# Analog_Testbed.net
KiCad netlist of a schematic drawn in Altium Designer
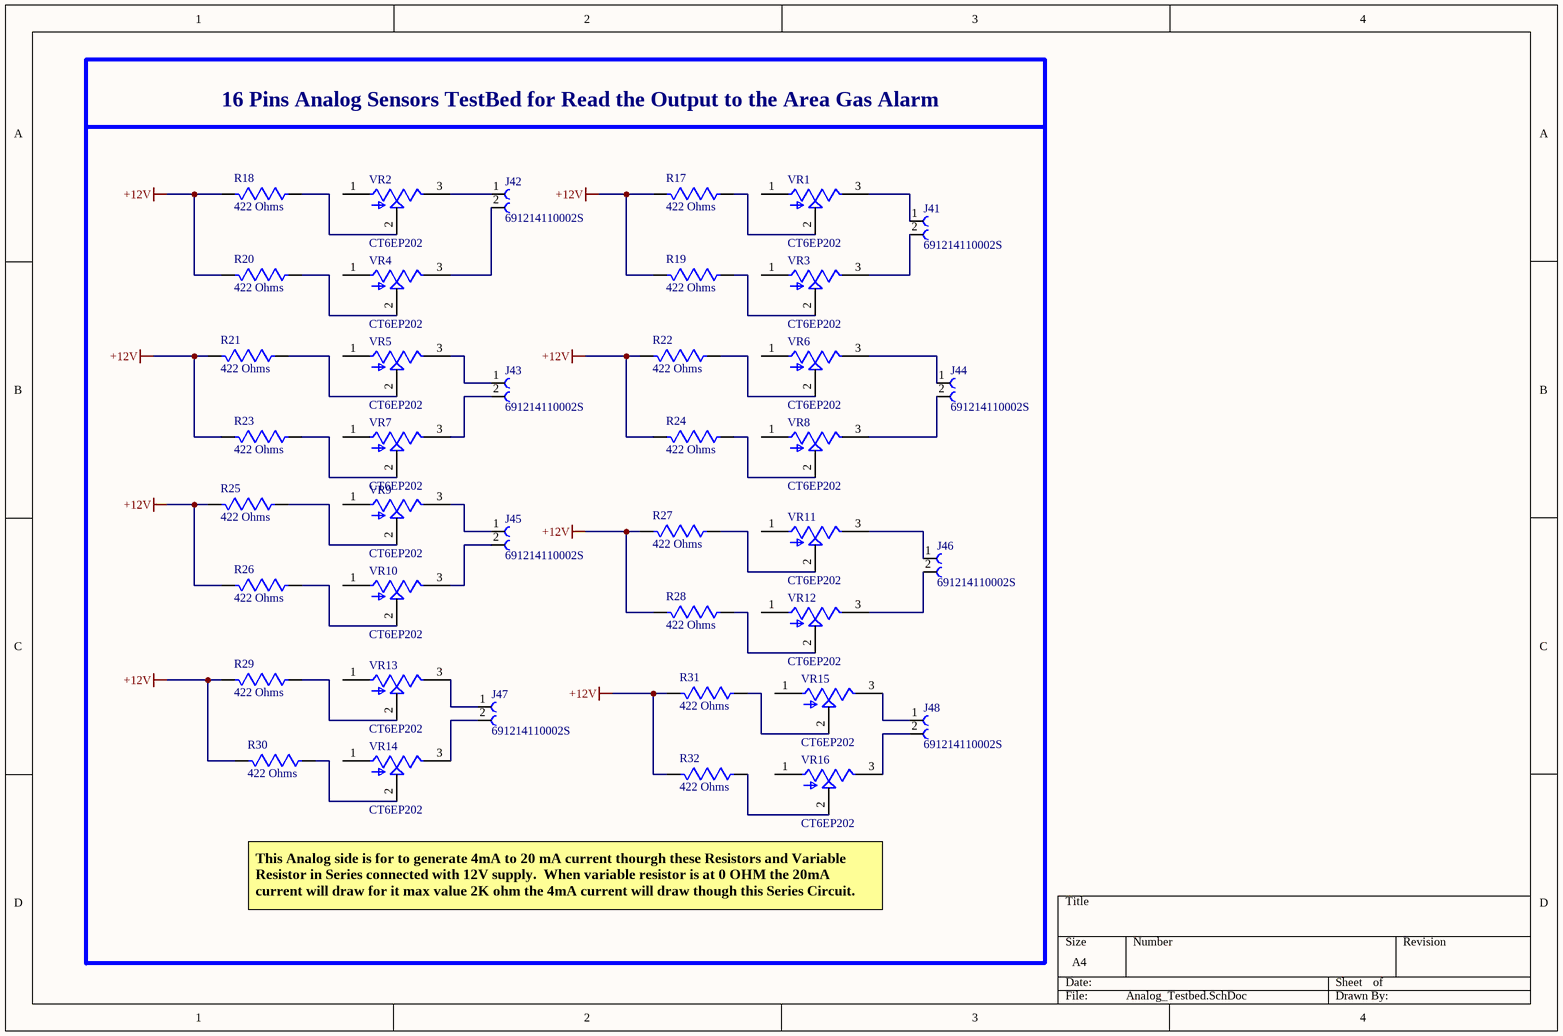
[diagram p0: Analog_Testbed.SchDoc]

(export (version "E")
  (design (tool "Eeschema 10.0.6"))
  (components
    (comp (ref "J41")
      (value "691214110002S")
      (footprint "691214110002S")
      (description "2 Position Wire to Board Terminal Block Horizontal with Board 0.138 (3.50mm) Through Hole")
      (fields (field (name "MF") "WÃ¼rth Elektronik"))
      (libsource (lib "Schlib1") (part "691214110002S"))
    )
    (comp (ref "J42")
      (value "691214110002S")
      (footprint "691214110002S")
      (description "2 Position Wire to Board Terminal Block Horizontal with Board 0.138 (3.50mm) Through Hole")
      (fields (field (name "MF") "WÃ¼rth Elektronik"))
      (libsource (lib "Schlib1") (part "691214110002S"))
    )
    (comp (ref "J43")
      (value "691214110002S")
      (footprint "691214110002S")
      (description "2 Position Wire to Board Terminal Block Horizontal with Board 0.138 (3.50mm) Through Hole")
      (fields (field (name "MF") "WÃ¼rth Elektronik"))
      (libsource (lib "Schlib1") (part "691214110002S"))
    )
    (comp (ref "J44")
      (value "691214110002S")
      (footprint "691214110002S")
      (description "2 Position Wire to Board Terminal Block Horizontal with Board 0.138 (3.50mm) Through Hole")
      (fields (field (name "MF") "WÃ¼rth Elektronik"))
      (libsource (lib "Schlib1") (part "691214110002S"))
    )
    (comp (ref "J45")
      (value "691214110002S")
      (footprint "691214110002S")
      (description "2 Position Wire to Board Terminal Block Horizontal with Board 0.138 (3.50mm) Through Hole")
      (fields (field (name "MF") "WÃ¼rth Elektronik"))
      (libsource (lib "Schlib1") (part "691214110002S"))
    )
    (comp (ref "J46")
      (value "691214110002S")
      (footprint "691214110002S")
      (description "2 Position Wire to Board Terminal Block Horizontal with Board 0.138 (3.50mm) Through Hole")
      (fields (field (name "MF") "WÃ¼rth Elektronik"))
      (libsource (lib "Schlib1") (part "691214110002S"))
    )
    (comp (ref "J47")
      (value "691214110002S")
      (footprint "691214110002S")
      (description "2 Position Wire to Board Terminal Block Horizontal with Board 0.138 (3.50mm) Through Hole")
      (fields (field (name "MF") "WÃ¼rth Elektronik"))
      (libsource (lib "Schlib1") (part "691214110002S"))
    )
    (comp (ref "J48")
      (value "691214110002S")
      (footprint "691214110002S")
      (description "2 Position Wire to Board Terminal Block Horizontal with Board 0.138 (3.50mm) Through Hole")
      (fields (field (name "MF") "WÃ¼rth Elektronik"))
      (libsource (lib "Schlib1") (part "691214110002S"))
    )
    (comp (ref "R17")
      (value "422 Ohms")
      (footprint "RES_422")
      (description "1W Thick Film Resistors 200V ±100ppm/℃ ±1% -55℃~+155℃ 422Ω 2512 Chip Resistor - Surface Mount ROHS")
      (libsource (lib "Schlib1") (part "RES_422"))
    )
    (comp (ref "R18")
      (value "422 Ohms")
      (footprint "RES_422")
      (description "1W Thick Film Resistors 200V ±100ppm/℃ ±1% -55℃~+155℃ 422Ω 2512 Chip Resistor - Surface Mount ROHS")
      (libsource (lib "Schlib1") (part "RES_422"))
    )
    (comp (ref "R19")
      (value "422 Ohms")
      (footprint "RES_422")
      (description "1W Thick Film Resistors 200V ±100ppm/℃ ±1% -55℃~+155℃ 422Ω 2512 Chip Resistor - Surface Mount ROHS")
      (libsource (lib "Schlib1") (part "RES_422"))
    )
    (comp (ref "R20")
      (value "422 Ohms")
      (footprint "RES_422")
      (description "1W Thick Film Resistors 200V ±100ppm/℃ ±1% -55℃~+155℃ 422Ω 2512 Chip Resistor - Surface Mount ROHS")
      (libsource (lib "Schlib1") (part "RES_422"))
    )
    (comp (ref "R21")
      (value "422 Ohms")
      (footprint "RES_422")
      (description "1W Thick Film Resistors 200V ±100ppm/℃ ±1% -55℃~+155℃ 422Ω 2512 Chip Resistor - Surface Mount ROHS")
      (libsource (lib "Schlib1") (part "RES_422"))
    )
    (comp (ref "R22")
      (value "422 Ohms")
      (footprint "RES_422")
      (description "1W Thick Film Resistors 200V ±100ppm/℃ ±1% -55℃~+155℃ 422Ω 2512 Chip Resistor - Surface Mount ROHS")
      (libsource (lib "Schlib1") (part "RES_422"))
    )
    (comp (ref "R23")
      (value "422 Ohms")
      (footprint "RES_422")
      (description "1W Thick Film Resistors 200V ±100ppm/℃ ±1% -55℃~+155℃ 422Ω 2512 Chip Resistor - Surface Mount ROHS")
      (libsource (lib "Schlib1") (part "RES_422"))
    )
    (comp (ref "R24")
      (value "422 Ohms")
      (footprint "RES_422")
      (description "1W Thick Film Resistors 200V ±100ppm/℃ ±1% -55℃~+155℃ 422Ω 2512 Chip Resistor - Surface Mount ROHS")
      (libsource (lib "Schlib1") (part "RES_422"))
    )
    (comp (ref "R25")
      (value "422 Ohms")
      (footprint "RES_422")
      (description "1W Thick Film Resistors 200V ±100ppm/℃ ±1% -55℃~+155℃ 422Ω 2512 Chip Resistor - Surface Mount ROHS")
      (libsource (lib "Schlib1") (part "RES_422"))
    )
    (comp (ref "R26")
      (value "422 Ohms")
      (footprint "RES_422")
      (description "1W Thick Film Resistors 200V ±100ppm/℃ ±1% -55℃~+155℃ 422Ω 2512 Chip Resistor - Surface Mount ROHS")
      (libsource (lib "Schlib1") (part "RES_422"))
    )
    (comp (ref "R27")
      (value "422 Ohms")
      (footprint "RES_422")
      (description "1W Thick Film Resistors 200V ±100ppm/℃ ±1% -55℃~+155℃ 422Ω 2512 Chip Resistor - Surface Mount ROHS")
      (libsource (lib "Schlib1") (part "RES_422"))
    )
    (comp (ref "R28")
      (value "422 Ohms")
      (footprint "RES_422")
      (description "1W Thick Film Resistors 200V ±100ppm/℃ ±1% -55℃~+155℃ 422Ω 2512 Chip Resistor - Surface Mount ROHS")
      (libsource (lib "Schlib1") (part "RES_422"))
    )
    (comp (ref "R29")
      (value "422 Ohms")
      (footprint "RES_422")
      (description "1W Thick Film Resistors 200V ±100ppm/℃ ±1% -55℃~+155℃ 422Ω 2512 Chip Resistor - Surface Mount ROHS")
      (libsource (lib "Schlib1") (part "RES_422"))
    )
    (comp (ref "R30")
      (value "422 Ohms")
      (footprint "RES_422")
      (description "1W Thick Film Resistors 200V ±100ppm/℃ ±1% -55℃~+155℃ 422Ω 2512 Chip Resistor - Surface Mount ROHS")
      (libsource (lib "Schlib1") (part "RES_422"))
    )
    (comp (ref "R31")
      (value "422 Ohms")
      (footprint "RES_422")
      (description "1W Thick Film Resistors 200V ±100ppm/℃ ±1% -55℃~+155℃ 422Ω 2512 Chip Resistor - Surface Mount ROHS")
      (libsource (lib "Schlib1") (part "RES_422"))
    )
    (comp (ref "R32")
      (value "422 Ohms")
      (footprint "RES_422")
      (description "1W Thick Film Resistors 200V ±100ppm/℃ ±1% -55℃~+155℃ 422Ω 2512 Chip Resistor - Surface Mount ROHS")
      (libsource (lib "Schlib1") (part "RES_422"))
    )
    (comp (ref "VR1") (value "CT6EP202") (footprint "CT6EP202") (libsource (lib "Schlib1") (part "CT6EP202")))
    (comp (ref "VR2") (value "CT6EP202") (footprint "CT6EP202") (libsource (lib "Schlib1") (part "CT6EP202")))
    (comp (ref "VR3") (value "CT6EP202") (footprint "CT6EP202") (libsource (lib "Schlib1") (part "CT6EP202")))
    (comp (ref "VR4") (value "CT6EP202") (footprint "CT6EP202") (libsource (lib "Schlib1") (part "CT6EP202")))
    (comp (ref "VR5") (value "CT6EP202") (footprint "CT6EP202") (libsource (lib "Schlib1") (part "CT6EP202")))
    (comp (ref "VR6") (value "CT6EP202") (footprint "CT6EP202") (libsource (lib "Schlib1") (part "CT6EP202")))
    (comp (ref "VR7") (value "CT6EP202") (footprint "CT6EP202") (libsource (lib "Schlib1") (part "CT6EP202")))
    (comp (ref "VR8") (value "CT6EP202") (footprint "CT6EP202") (libsource (lib "Schlib1") (part "CT6EP202")))
    (comp (ref "VR9") (value "CT6EP202") (footprint "CT6EP202") (libsource (lib "Schlib1") (part "CT6EP202")))
    (comp (ref "VR10")
      (value "CT6EP202")
      (footprint "CT6EP202")
      (libsource (lib "Schlib1") (part "CT6EP202"))
    )
    (comp (ref "VR11")
      (value "CT6EP202")
      (footprint "CT6EP202")
      (libsource (lib "Schlib1") (part "CT6EP202"))
    )
    (comp (ref "VR12")
      (value "CT6EP202")
      (footprint "CT6EP202")
      (libsource (lib "Schlib1") (part "CT6EP202"))
    )
    (comp (ref "VR13")
      (value "CT6EP202")
      (footprint "CT6EP202")
      (libsource (lib "Schlib1") (part "CT6EP202"))
    )
    (comp (ref "VR14")
      (value "CT6EP202")
      (footprint "CT6EP202")
      (libsource (lib "Schlib1") (part "CT6EP202"))
    )
    (comp (ref "VR15")
      (value "CT6EP202")
      (footprint "CT6EP202")
      (libsource (lib "Schlib1") (part "CT6EP202"))
    )
    (comp (ref "VR16")
      (value "CT6EP202")
      (footprint "CT6EP202")
      (libsource (lib "Schlib1") (part "CT6EP202"))
    )
  )
  (nets
    (net (code "1") (name "+12V") (class "Default")
      (node (ref "R17") (pin "1") (pinfunction "CCW_1") (pintype "passive"))
      (node (ref "R18") (pin "1") (pinfunction "CCW_1") (pintype "passive"))
      (node (ref "R19") (pin "1") (pinfunction "CCW_1") (pintype "passive"))
      (node (ref "R20") (pin "1") (pinfunction "CCW_1") (pintype "passive"))
      (node (ref "R21") (pin "1") (pinfunction "CCW_1") (pintype "passive"))
      (node (ref "R22") (pin "1") (pinfunction "CCW_1") (pintype "passive"))
      (node (ref "R23") (pin "1") (pinfunction "CCW_1") (pintype "passive"))
      (node (ref "R24") (pin "1") (pinfunction "CCW_1") (pintype "passive"))
      (node (ref "R25") (pin "1") (pinfunction "CCW_1") (pintype "passive"))
      (node (ref "R26") (pin "1") (pinfunction "CCW_1") (pintype "passive"))
      (node (ref "R27") (pin "1") (pinfunction "CCW_1") (pintype "passive"))
      (node (ref "R28") (pin "1") (pinfunction "CCW_1") (pintype "passive"))
      (node (ref "R29") (pin "1") (pinfunction "CCW_1") (pintype "passive"))
      (node (ref "R30") (pin "1") (pinfunction "CCW_1") (pintype "passive"))
      (node (ref "R31") (pin "1") (pinfunction "CCW_1") (pintype "passive"))
      (node (ref "R32") (pin "1") (pinfunction "CCW_1") (pintype "passive"))
    )
    (net (code "2") (name "Net-(R17-CW)") (class "Default")
      (node (ref "R17") (pin "2") (pinfunction "CW_2") (pintype "passive"))
      (node (ref "VR1") (pin "2") (pinfunction "WIPER_2") (pintype "passive"))
    )
    (net (code "3") (name "Net-(R18-CW)") (class "Default")
      (node (ref "R18") (pin "2") (pinfunction "CW_2") (pintype "passive"))
      (node (ref "VR2") (pin "2") (pinfunction "WIPER_2") (pintype "passive"))
    )
    (net (code "4") (name "Net-(R19-CW)") (class "Default")
      (node (ref "R19") (pin "2") (pinfunction "CW_2") (pintype "passive"))
      (node (ref "VR3") (pin "2") (pinfunction "WIPER_2") (pintype "passive"))
    )
    (net (code "5") (name "Net-(R20-CW)") (class "Default")
      (node (ref "R20") (pin "2") (pinfunction "CW_2") (pintype "passive"))
      (node (ref "VR4") (pin "2") (pinfunction "WIPER_2") (pintype "passive"))
    )
    (net (code "6") (name "Net-(R21-CW)") (class "Default")
      (node (ref "R21") (pin "2") (pinfunction "CW_2") (pintype "passive"))
      (node (ref "VR5") (pin "2") (pinfunction "WIPER_2") (pintype "passive"))
    )
    (net (code "7") (name "Net-(R22-CW)") (class "Default")
      (node (ref "R22") (pin "2") (pinfunction "CW_2") (pintype "passive"))
      (node (ref "VR6") (pin "2") (pinfunction "WIPER_2") (pintype "passive"))
    )
    (net (code "8") (name "Net-(R23-CW)") (class "Default")
      (node (ref "R23") (pin "2") (pinfunction "CW_2") (pintype "passive"))
      (node (ref "VR7") (pin "2") (pinfunction "WIPER_2") (pintype "passive"))
    )
    (net (code "9") (name "Net-(R24-CW)") (class "Default")
      (node (ref "R24") (pin "2") (pinfunction "CW_2") (pintype "passive"))
      (node (ref "VR8") (pin "2") (pinfunction "WIPER_2") (pintype "passive"))
    )
    (net (code "10") (name "Net-(R25-CW)") (class "Default")
      (node (ref "R25") (pin "2") (pinfunction "CW_2") (pintype "passive"))
      (node (ref "VR9") (pin "2") (pinfunction "WIPER_2") (pintype "passive"))
    )
    (net (code "11") (name "Net-(R26-CW)") (class "Default")
      (node (ref "R26") (pin "2") (pinfunction "CW_2") (pintype "passive"))
      (node (ref "VR10") (pin "2") (pinfunction "WIPER_2") (pintype "passive"))
    )
    (net (code "12") (name "Net-(R27-CW)") (class "Default")
      (node (ref "R27") (pin "2") (pinfunction "CW_2") (pintype "passive"))
      (node (ref "VR11") (pin "2") (pinfunction "WIPER_2") (pintype "passive"))
    )
    (net (code "13") (name "Net-(R28-CW)") (class "Default")
      (node (ref "R28") (pin "2") (pinfunction "CW_2") (pintype "passive"))
      (node (ref "VR12") (pin "2") (pinfunction "WIPER_2") (pintype "passive"))
    )
    (net (code "14") (name "Net-(R29-CW)") (class "Default")
      (node (ref "R29") (pin "2") (pinfunction "CW_2") (pintype "passive"))
      (node (ref "VR13") (pin "2") (pinfunction "WIPER_2") (pintype "passive"))
    )
    (net (code "15") (name "Net-(R30-CW)") (class "Default")
      (node (ref "R30") (pin "2") (pinfunction "CW_2") (pintype "passive"))
      (node (ref "VR14") (pin "2") (pinfunction "WIPER_2") (pintype "passive"))
    )
    (net (code "16") (name "Net-(R31-CW)") (class "Default")
      (node (ref "R31") (pin "2") (pinfunction "CW_2") (pintype "passive"))
      (node (ref "VR15") (pin "2") (pinfunction "WIPER_2") (pintype "passive"))
    )
    (net (code "17") (name "Net-(R32-CW)") (class "Default")
      (node (ref "R32") (pin "2") (pinfunction "CW_2") (pintype "passive"))
      (node (ref "VR16") (pin "2") (pinfunction "WIPER_2") (pintype "passive"))
    )
    (net (code "18") (name "Net-(VR1-CW)") (class "Default")
      (node (ref "J41") (pin "1") (pinfunction "1_1") (pintype "passive"))
      (node (ref "VR1") (pin "3") (pinfunction "CW_3") (pintype "passive"))
    )
    (net (code "19") (name "Net-(VR2-CW)") (class "Default")
      (node (ref "J42") (pin "1") (pinfunction "1_1") (pintype "passive"))
      (node (ref "VR2") (pin "3") (pinfunction "CW_3") (pintype "passive"))
    )
    (net (code "20") (name "Net-(VR3-CW)") (class "Default")
      (node (ref "J41") (pin "2") (pinfunction "2_2") (pintype "passive"))
      (node (ref "VR3") (pin "3") (pinfunction "CW_3") (pintype "passive"))
    )
    (net (code "21") (name "Net-(VR4-CW)") (class "Default")
      (node (ref "J42") (pin "2") (pinfunction "2_2") (pintype "passive"))
      (node (ref "VR4") (pin "3") (pinfunction "CW_3") (pintype "passive"))
    )
    (net (code "22") (name "Net-(VR5-CW)") (class "Default")
      (node (ref "J43") (pin "1") (pinfunction "1_1") (pintype "passive"))
      (node (ref "VR5") (pin "3") (pinfunction "CW_3") (pintype "passive"))
    )
    (net (code "23") (name "Net-(VR6-CW)") (class "Default")
      (node (ref "J44") (pin "1") (pinfunction "1_1") (pintype "passive"))
      (node (ref "VR6") (pin "3") (pinfunction "CW_3") (pintype "passive"))
    )
    (net (code "24") (name "Net-(VR7-CW)") (class "Default")
      (node (ref "J43") (pin "2") (pinfunction "2_2") (pintype "passive"))
      (node (ref "VR7") (pin "3") (pinfunction "CW_3") (pintype "passive"))
    )
    (net (code "25") (name "Net-(VR8-CW)") (class "Default")
      (node (ref "J44") (pin "2") (pinfunction "2_2") (pintype "passive"))
      (node (ref "VR8") (pin "3") (pinfunction "CW_3") (pintype "passive"))
    )
    (net (code "26") (name "Net-(VR9-CW)") (class "Default")
      (node (ref "J45") (pin "1") (pinfunction "1_1") (pintype "passive"))
      (node (ref "VR9") (pin "3") (pinfunction "CW_3") (pintype "passive"))
    )
    (net (code "27") (name "Net-(VR10-CW)") (class "Default")
      (node (ref "J45") (pin "2") (pinfunction "2_2") (pintype "passive"))
      (node (ref "VR10") (pin "3") (pinfunction "CW_3") (pintype "passive"))
    )
    (net (code "28") (name "Net-(VR11-CW)") (class "Default")
      (node (ref "J46") (pin "1") (pinfunction "1_1") (pintype "passive"))
      (node (ref "VR11") (pin "3") (pinfunction "CW_3") (pintype "passive"))
    )
    (net (code "29") (name "Net-(VR12-CW)") (class "Default")
      (node (ref "J46") (pin "2") (pinfunction "2_2") (pintype "passive"))
      (node (ref "VR12") (pin "3") (pinfunction "CW_3") (pintype "passive"))
    )
    (net (code "30") (name "Net-(VR13-CW)") (class "Default")
      (node (ref "J47") (pin "1") (pinfunction "1_1") (pintype "passive"))
      (node (ref "VR13") (pin "3") (pinfunction "CW_3") (pintype "passive"))
    )
    (net (code "31") (name "Net-(VR14-CW)") (class "Default")
      (node (ref "J47") (pin "2") (pinfunction "2_2") (pintype "passive"))
      (node (ref "VR14") (pin "3") (pinfunction "CW_3") (pintype "passive"))
    )
    (net (code "32") (name "Net-(VR15-CW)") (class "Default")
      (node (ref "J48") (pin "1") (pinfunction "1_1") (pintype "passive"))
      (node (ref "VR15") (pin "3") (pinfunction "CW_3") (pintype "passive"))
    )
    (net (code "33") (name "Net-(VR16-CW)") (class "Default")
      (node (ref "J48") (pin "2") (pinfunction "2_2") (pintype "passive"))
      (node (ref "VR16") (pin "3") (pinfunction "CW_3") (pintype "passive"))
    )
    (net (code "34") (name "unconnected-(VR1-CCW-Pad1)") (class "Default")
      (node (ref "VR1") (pin "1") (pinfunction "CCW_1") (pintype "passive"))
    )
    (net (code "35") (name "unconnected-(VR2-CCW-Pad1)") (class "Default")
      (node (ref "VR2") (pin "1") (pinfunction "CCW_1") (pintype "passive"))
    )
    (net (code "36") (name "unconnected-(VR3-CCW-Pad1)") (class "Default")
      (node (ref "VR3") (pin "1") (pinfunction "CCW_1") (pintype "passive"))
    )
    (net (code "37") (name "unconnected-(VR4-CCW-Pad1)") (class "Default")
      (node (ref "VR4") (pin "1") (pinfunction "CCW_1") (pintype "passive"))
    )
    (net (code "38") (name "unconnected-(VR5-CCW-Pad1)") (class "Default")
      (node (ref "VR5") (pin "1") (pinfunction "CCW_1") (pintype "passive"))
    )
    (net (code "39") (name "unconnected-(VR6-CCW-Pad1)") (class "Default")
      (node (ref "VR6") (pin "1") (pinfunction "CCW_1") (pintype "passive"))
    )
    (net (code "40") (name "unconnected-(VR7-CCW-Pad1)") (class "Default")
      (node (ref "VR7") (pin "1") (pinfunction "CCW_1") (pintype "passive"))
    )
    (net (code "41") (name "unconnected-(VR8-CCW-Pad1)") (class "Default")
      (node (ref "VR8") (pin "1") (pinfunction "CCW_1") (pintype "passive"))
    )
    (net (code "42") (name "unconnected-(VR9-CCW-Pad1)") (class "Default")
      (node (ref "VR9") (pin "1") (pinfunction "CCW_1") (pintype "passive"))
    )
    (net (code "43") (name "unconnected-(VR10-CCW-Pad1)") (class "Default")
      (node (ref "VR10") (pin "1") (pinfunction "CCW_1") (pintype "passive"))
    )
    (net (code "44") (name "unconnected-(VR11-CCW-Pad1)") (class "Default")
      (node (ref "VR11") (pin "1") (pinfunction "CCW_1") (pintype "passive"))
    )
    (net (code "45") (name "unconnected-(VR12-CCW-Pad1)") (class "Default")
      (node (ref "VR12") (pin "1") (pinfunction "CCW_1") (pintype "passive"))
    )
    (net (code "46") (name "unconnected-(VR13-CCW-Pad1)") (class "Default")
      (node (ref "VR13") (pin "1") (pinfunction "CCW_1") (pintype "passive"))
    )
    (net (code "47") (name "unconnected-(VR14-CCW-Pad1)") (class "Default")
      (node (ref "VR14") (pin "1") (pinfunction "CCW_1") (pintype "passive"))
    )
    (net (code "48") (name "unconnected-(VR15-CCW-Pad1)") (class "Default")
      (node (ref "VR15") (pin "1") (pinfunction "CCW_1") (pintype "passive"))
    )
    (net (code "49") (name "unconnected-(VR16-CCW-Pad1)") (class "Default")
      (node (ref "VR16") (pin "1") (pinfunction "CCW_1") (pintype "passive"))
    )
  )
)
